# Design_final.net
KiCad netlist of a schematic drawn in EAGLE
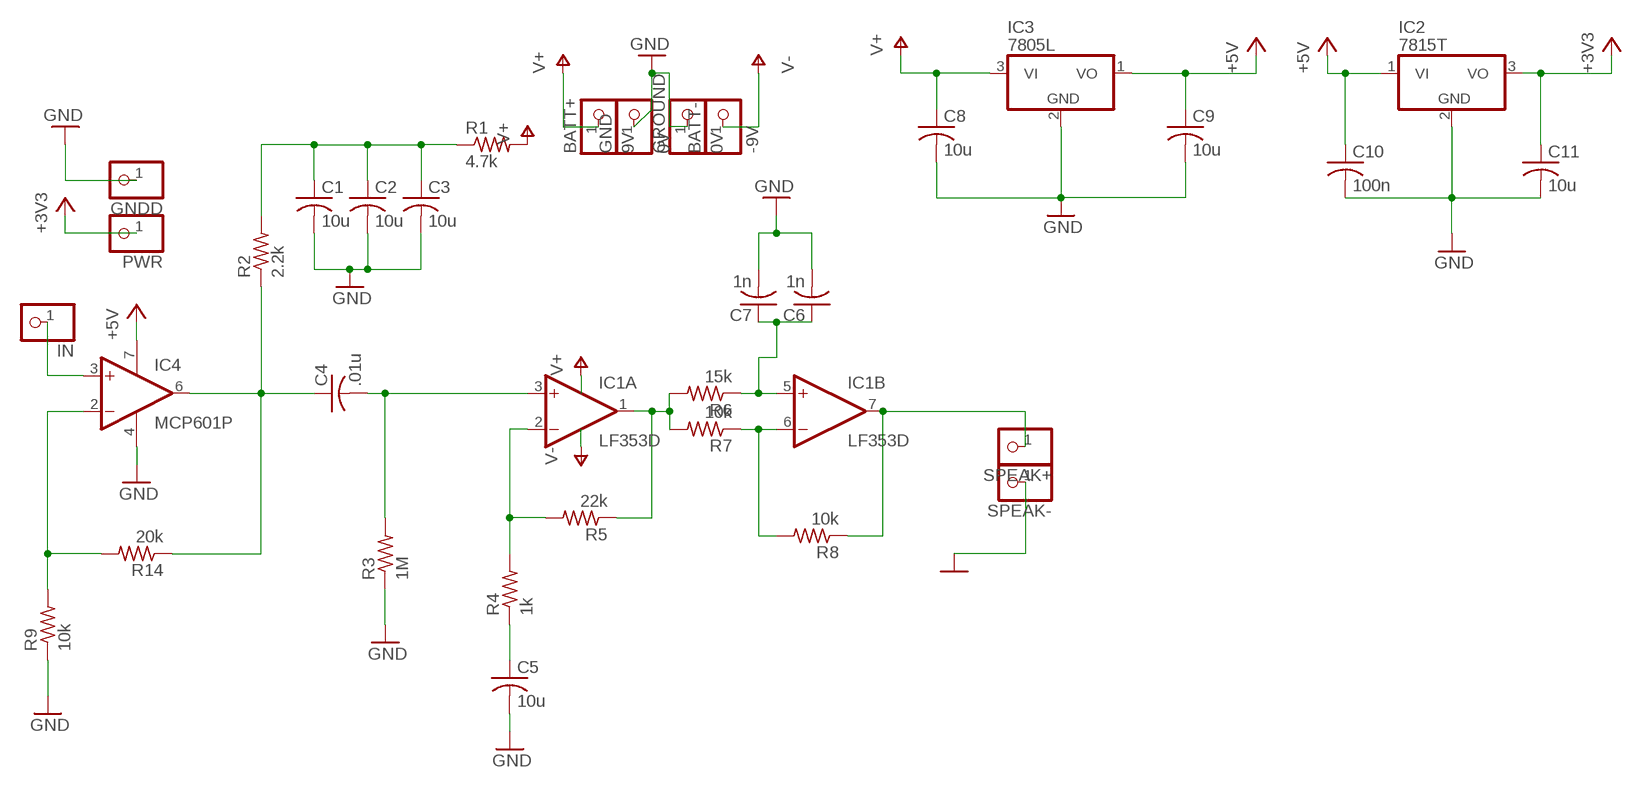
[diagram p0: schematic, sheet 1]

(export (version "E")
  (design (tool "Eeschema 10.0.6"))
  (components
    (comp (ref "BATT+")
      (value "9V")
      (footprint "eagle-import:1X01")
      (libsource (lib "eagle-import") (part "PINHD-1X1"))
    )
    (comp (ref "BATT-")
      (value "-9V")
      (footprint "eagle-import:1X01")
      (libsource (lib "eagle-import") (part "PINHD-1X1"))
    )
    (comp (ref "C1")
      (value "10u")
      (footprint "eagle-import:C0805")
      (libsource (lib "eagle-import") (part "C-USC0805"))
    )
    (comp (ref "C2")
      (value "10u")
      (footprint "eagle-import:C0805")
      (libsource (lib "eagle-import") (part "C-USC0805"))
    )
    (comp (ref "C3")
      (value "10u")
      (footprint "eagle-import:C0805")
      (libsource (lib "eagle-import") (part "C-USC0805"))
    )
    (comp (ref "C4")
      (value ".01u")
      (footprint "eagle-import:C0805")
      (libsource (lib "eagle-import") (part "C-USC0805"))
    )
    (comp (ref "C5")
      (value "10u")
      (footprint "eagle-import:C0805")
      (libsource (lib "eagle-import") (part "C-USC0805"))
    )
    (comp (ref "C6")
      (value "1n")
      (footprint "eagle-import:C0805")
      (libsource (lib "eagle-import") (part "C-USC0805"))
    )
    (comp (ref "C7")
      (value "1n")
      (footprint "eagle-import:C0805")
      (libsource (lib "eagle-import") (part "C-USC0805"))
    )
    (comp (ref "C8")
      (value "10u")
      (footprint "eagle-import:C0805")
      (libsource (lib "eagle-import") (part "C-USC0805"))
    )
    (comp (ref "C9")
      (value "10u")
      (footprint "eagle-import:C0805")
      (libsource (lib "eagle-import") (part "C-USC0805"))
    )
    (comp (ref "C10")
      (value "100n")
      (footprint "eagle-import:C0805")
      (libsource (lib "eagle-import") (part "C-USC0805"))
    )
    (comp (ref "C11")
      (value "10u")
      (footprint "eagle-import:C0805")
      (libsource (lib "eagle-import") (part "C-USC0805"))
    )
    (comp (ref "GND")
      (value "0V")
      (footprint "eagle-import:1X01")
      (libsource (lib "eagle-import") (part "PINHD-1X1"))
    )
    (comp (ref "GNDD")
      (value "PINHD-1X1")
      (footprint "eagle-import:1X01")
      (libsource (lib "eagle-import") (part "PINHD-1X1"))
    )
    (comp (ref "GROUND")
      (value "0V")
      (footprint "eagle-import:1X01")
      (libsource (lib "eagle-import") (part "PINHD-1X1"))
    )
    (comp (ref "IC1")
      (value "LF353D")
      (footprint "eagle-import:SO08")
      (libsource (lib "eagle-import") (part "LF353D"))
    )
    (comp (ref "IC2")
      (value "7815T")
      (footprint "eagle-import:TO220H")
      (libsource (lib "eagle-import") (part "78T15"))
    )
    (comp (ref "IC3")
      (value "7805L")
      (footprint "eagle-import:TO92")
      (libsource (lib "eagle-import") (part "78L05"))
    )
    (comp (ref "IC4")
      (value "MCP601P")
      (footprint "eagle-import:DIL08")
      (libsource (lib "eagle-import") (part "MCP601P"))
    )
    (comp (ref "IN")
      (value "PINHD-1X1")
      (footprint "eagle-import:1X01")
      (libsource (lib "eagle-import") (part "PINHD-1X1"))
    )
    (comp (ref "PWR")
      (value "PINHD-1X1")
      (footprint "eagle-import:1X01")
      (libsource (lib "eagle-import") (part "PINHD-1X1"))
    )
    (comp (ref "R1")
      (value "4.7k")
      (footprint "eagle-import:M0805")
      (libsource (lib "eagle-import") (part "R-US_M0805"))
    )
    (comp (ref "R2")
      (value "2.2k")
      (footprint "eagle-import:M0805")
      (libsource (lib "eagle-import") (part "R-US_M0805"))
    )
    (comp (ref "R3")
      (value "1M")
      (footprint "eagle-import:M0805")
      (libsource (lib "eagle-import") (part "R-US_M0805"))
    )
    (comp (ref "R4")
      (value "1k")
      (footprint "eagle-import:M0805")
      (libsource (lib "eagle-import") (part "R-US_M0805"))
    )
    (comp (ref "R5")
      (value "22k")
      (footprint "eagle-import:M0805")
      (libsource (lib "eagle-import") (part "R-US_M0805"))
    )
    (comp (ref "R6")
      (value "15k")
      (footprint "eagle-import:M0805")
      (libsource (lib "eagle-import") (part "R-US_M0805"))
    )
    (comp (ref "R7")
      (value "10k")
      (footprint "eagle-import:M0805")
      (libsource (lib "eagle-import") (part "R-US_M0805"))
    )
    (comp (ref "R8")
      (value "10k")
      (footprint "eagle-import:M0805")
      (libsource (lib "eagle-import") (part "R-US_M0805"))
    )
    (comp (ref "R9")
      (value "10k")
      (footprint "eagle-import:M0805")
      (libsource (lib "eagle-import") (part "R-US_M0805"))
    )
    (comp (ref "R14")
      (value "20k")
      (footprint "eagle-import:M0805")
      (libsource (lib "eagle-import") (part "R-US_M0805"))
    )
    (comp (ref "SPEAK+")
      (value "PINHD-1X1")
      (footprint "eagle-import:1X01")
      (libsource (lib "eagle-import") (part "PINHD-1X1"))
    )
    (comp (ref "SPEAK-")
      (value "PINHD-1X1")
      (footprint "eagle-import:1X01")
      (libsource (lib "eagle-import") (part "PINHD-1X1"))
    )
  )
  (nets
    (net (code "1") (name "+3V3") (class "Default")
      (node (ref "C11") (pin "1") (pinfunction "1_1") (pintype "passive"))
      (node (ref "IC2") (pin "3") (pinfunction "VO_3") (pintype "passive"))
      (node (ref "PWR") (pin "1") (pinfunction "1_1") (pintype "passive"))
    )
    (net (code "2") (name "+5V") (class "Default")
      (node (ref "C10") (pin "1") (pinfunction "1_1") (pintype "passive"))
      (node (ref "C9") (pin "1") (pinfunction "1_1") (pintype "passive"))
      (node (ref "IC2") (pin "1") (pinfunction "VI_1") (pintype "input"))
      (node (ref "IC3") (pin "1") (pinfunction "VO_1") (pintype "passive"))
      (node (ref "IC4") (pin "7") (pinfunction "V+_7") (pintype "power_in"))
    )
    (net (code "3") (name "GND") (class "Default")
      (node (ref "C1") (pin "2") (pinfunction "2_2") (pintype "passive"))
      (node (ref "C10") (pin "2") (pinfunction "2_2") (pintype "passive"))
      (node (ref "C11") (pin "2") (pinfunction "2_2") (pintype "passive"))
      (node (ref "C2") (pin "2") (pinfunction "2_2") (pintype "passive"))
      (node (ref "C3") (pin "2") (pinfunction "2_2") (pintype "passive"))
      (node (ref "C5") (pin "2") (pinfunction "2_2") (pintype "passive"))
      (node (ref "C6") (pin "2") (pinfunction "2_2") (pintype "passive"))
      (node (ref "C7") (pin "2") (pinfunction "2_2") (pintype "passive"))
      (node (ref "C8") (pin "2") (pinfunction "2_2") (pintype "passive"))
      (node (ref "C9") (pin "2") (pinfunction "2_2") (pintype "passive"))
      (node (ref "GND") (pin "1") (pinfunction "1_1") (pintype "passive"))
      (node (ref "GNDD") (pin "1") (pinfunction "1_1") (pintype "passive"))
      (node (ref "GROUND") (pin "1") (pinfunction "1_1") (pintype "passive"))
      (node (ref "IC2") (pin "2") (pinfunction "GND_2") (pintype "passive"))
      (node (ref "IC3") (pin "2") (pinfunction "GND_2") (pintype "passive"))
      (node (ref "IC4") (pin "4") (pinfunction "V-_4") (pintype "power_in"))
      (node (ref "R3") (pin "1") (pinfunction "1_1") (pintype "passive"))
      (node (ref "R9") (pin "1") (pinfunction "1_1") (pintype "passive"))
      (node (ref "SPEAK-") (pin "1") (pinfunction "1_1") (pintype "passive"))
    )
    (net (code "4") (name "Net-(C1-Pad1)") (class "Default")
      (node (ref "C1") (pin "1") (pinfunction "1_1") (pintype "passive"))
      (node (ref "C2") (pin "1") (pinfunction "1_1") (pintype "passive"))
      (node (ref "C3") (pin "1") (pinfunction "1_1") (pintype "passive"))
      (node (ref "R1") (pin "1") (pinfunction "1_1") (pintype "passive"))
      (node (ref "R2") (pin "2") (pinfunction "2_2") (pintype "passive"))
    )
    (net (code "5") (name "Net-(C5-Pad1)") (class "Default")
      (node (ref "C5") (pin "1") (pinfunction "1_1") (pintype "passive"))
      (node (ref "R4") (pin "1") (pinfunction "1_1") (pintype "passive"))
    )
    (net (code "6") (name "Net-(IC1A-+IN)") (class "Default")
      (node (ref "C4") (pin "2") (pinfunction "2_2") (pintype "passive"))
      (node (ref "IC1") (pin "3") (pinfunction "+IN_3") (pintype "input"))
      (node (ref "R3") (pin "2") (pinfunction "2_2") (pintype "passive"))
    )
    (net (code "7") (name "Net-(IC1A--IN)") (class "Default")
      (node (ref "IC1") (pin "2") (pinfunction "-IN_2") (pintype "input"))
      (node (ref "R4") (pin "2") (pinfunction "2_2") (pintype "passive"))
      (node (ref "R5") (pin "2") (pinfunction "2_2") (pintype "passive"))
    )
    (net (code "8") (name "Net-(IC1A-OUT)") (class "Default")
      (node (ref "IC1") (pin "1") (pinfunction "OUT_1") (pintype "output"))
      (node (ref "R5") (pin "1") (pinfunction "1_1") (pintype "passive"))
      (node (ref "R6") (pin "2") (pinfunction "2_2") (pintype "passive"))
      (node (ref "R7") (pin "2") (pinfunction "2_2") (pintype "passive"))
    )
    (net (code "9") (name "Net-(IC1B-+IN)") (class "Default")
      (node (ref "C6") (pin "1") (pinfunction "1_1") (pintype "passive"))
      (node (ref "C7") (pin "1") (pinfunction "1_1") (pintype "passive"))
      (node (ref "IC1") (pin "5") (pinfunction "+IN_5") (pintype "input"))
      (node (ref "R6") (pin "1") (pinfunction "1_1") (pintype "passive"))
    )
    (net (code "10") (name "Net-(IC1B--IN)") (class "Default")
      (node (ref "IC1") (pin "6") (pinfunction "-IN_6") (pintype "input"))
      (node (ref "R7") (pin "1") (pinfunction "1_1") (pintype "passive"))
      (node (ref "R8") (pin "2") (pinfunction "2_2") (pintype "passive"))
    )
    (net (code "11") (name "Net-(IC1B-OUT)") (class "Default")
      (node (ref "IC1") (pin "7") (pinfunction "OUT_7") (pintype "output"))
      (node (ref "R8") (pin "1") (pinfunction "1_1") (pintype "passive"))
      (node (ref "SPEAK+") (pin "1") (pinfunction "1_1") (pintype "passive"))
    )
    (net (code "12") (name "Net-(IC4-+IN)") (class "Default")
      (node (ref "IC4") (pin "3") (pinfunction "+IN_3") (pintype "input"))
      (node (ref "IN") (pin "1") (pinfunction "1_1") (pintype "passive"))
    )
    (net (code "13") (name "Net-(IC4--IN)") (class "Default")
      (node (ref "IC4") (pin "2") (pinfunction "-IN_2") (pintype "input"))
      (node (ref "R14") (pin "2") (pinfunction "2_2") (pintype "passive"))
      (node (ref "R9") (pin "2") (pinfunction "2_2") (pintype "passive"))
    )
    (net (code "14") (name "Net-(IC4-OUT)") (class "Default")
      (node (ref "C4") (pin "1") (pinfunction "1_1") (pintype "passive"))
      (node (ref "IC4") (pin "6") (pinfunction "OUT_6") (pintype "output"))
      (node (ref "R14") (pin "1") (pinfunction "1_1") (pintype "passive"))
      (node (ref "R2") (pin "1") (pinfunction "1_1") (pintype "passive"))
    )
    (net (code "15") (name "V+") (class "Default")
      (node (ref "BATT+") (pin "1") (pinfunction "1_1") (pintype "passive"))
      (node (ref "C8") (pin "1") (pinfunction "1_1") (pintype "passive"))
      (node (ref "IC3") (pin "3") (pinfunction "VI_3") (pintype "input"))
      (node (ref "R1") (pin "2") (pinfunction "2_2") (pintype "passive"))
    )
    (net (code "16") (name "V-") (class "Default")
      (node (ref "BATT-") (pin "1") (pinfunction "1_1") (pintype "passive"))
    )
  )
)
